# TRV_MRF49_U_V1_1_BF.net
KiCad netlist of a schematic drawn in EAGLE
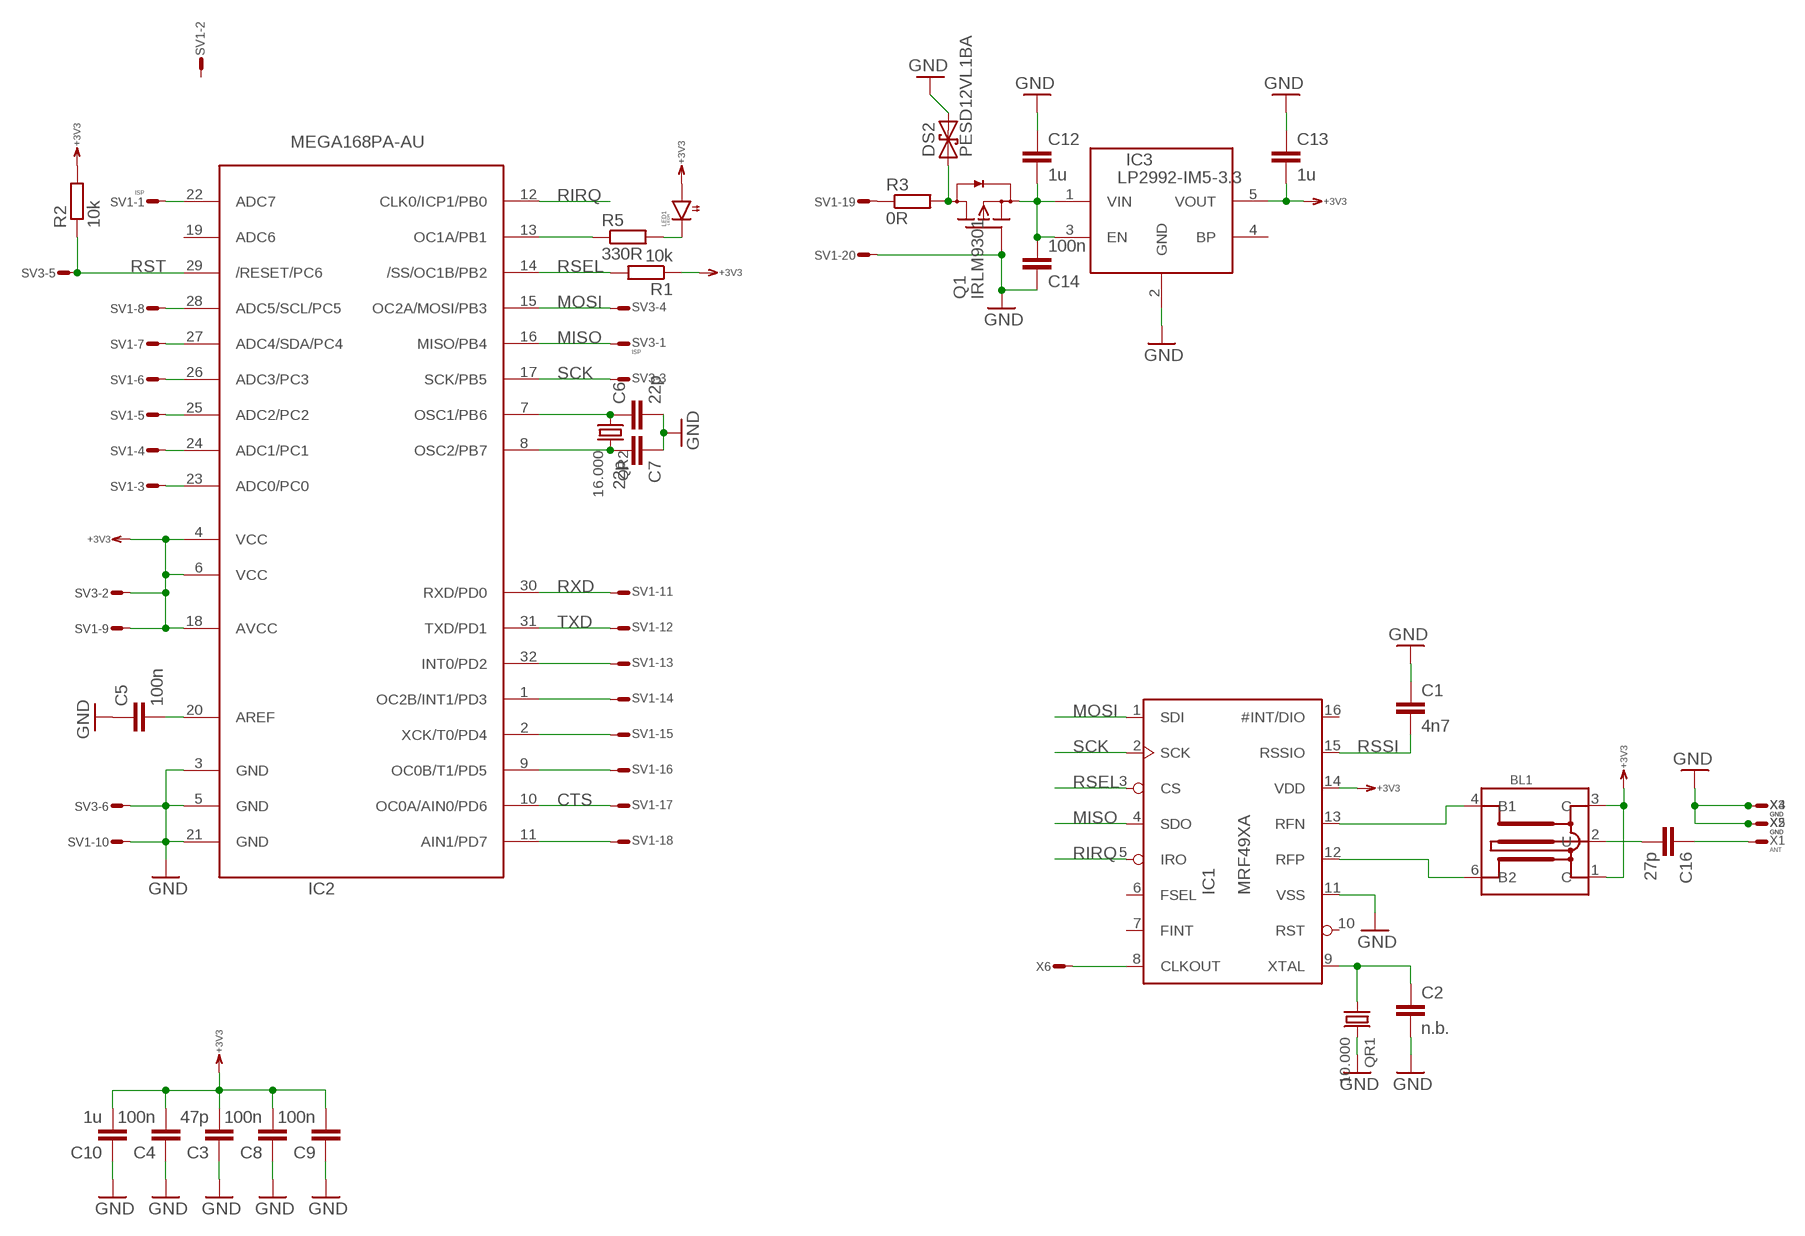
[diagram p0: schematic, sheet 1]

(export (version "E")
  (design (tool "Eeschema 10.0.6"))
  (components
    (comp (ref "BL1")
      (value "BL1")
      (footprint "eagle-import:BL")
      (libsource (lib "eagle-import") (part "BL1"))
    )
    (comp (ref "C1")
      (value "4n7")
      (footprint "eagle-import:0603")
      (libsource (lib "eagle-import") (part "C0603"))
    )
    (comp (ref "C2")
      (value "n.b.")
      (footprint "eagle-import:0603")
      (libsource (lib "eagle-import") (part "C0603"))
    )
    (comp (ref "C3")
      (value "47p")
      (footprint "eagle-import:0603")
      (libsource (lib "eagle-import") (part "C0603"))
    )
    (comp (ref "C4")
      (value "100n")
      (footprint "eagle-import:0603")
      (libsource (lib "eagle-import") (part "C0603"))
    )
    (comp (ref "C5")
      (value "100n")
      (footprint "eagle-import:0603")
      (libsource (lib "eagle-import") (part "C0603"))
    )
    (comp (ref "C6")
      (value "22p")
      (footprint "eagle-import:0603")
      (libsource (lib "eagle-import") (part "C0603"))
    )
    (comp (ref "C7")
      (value "22p")
      (footprint "eagle-import:0603")
      (libsource (lib "eagle-import") (part "C0603"))
    )
    (comp (ref "C8")
      (value "100n")
      (footprint "eagle-import:0603")
      (libsource (lib "eagle-import") (part "C0603"))
    )
    (comp (ref "C9")
      (value "100n")
      (footprint "eagle-import:0603")
      (libsource (lib "eagle-import") (part "C0603"))
    )
    (comp (ref "C10")
      (value "1u")
      (footprint "eagle-import:0603")
      (libsource (lib "eagle-import") (part "C0603"))
    )
    (comp (ref "C12")
      (value "1u")
      (footprint "eagle-import:0603")
      (libsource (lib "eagle-import") (part "C0603"))
    )
    (comp (ref "C13")
      (value "1u")
      (footprint "eagle-import:0603")
      (libsource (lib "eagle-import") (part "C0603"))
    )
    (comp (ref "C14")
      (value "100n")
      (footprint "eagle-import:0603")
      (libsource (lib "eagle-import") (part "C0603"))
    )
    (comp (ref "C16")
      (value "27p")
      (footprint "eagle-import:0603")
      (libsource (lib "eagle-import") (part "C0603"))
    )
    (comp (ref "DS2")
      (value "PESD12VL1BA")
      (footprint "eagle-import:SOD323")
      (libsource (lib "eagle-import") (part "TVS-U323"))
    )
    (comp (ref "IC1")
      (value "MRF49XA")
      (footprint "eagle-import:TSSOP16")
      (libsource (lib "eagle-import") (part "MRF49XA"))
    )
    (comp (ref "IC2")
      (value "MEGA168PA-AU")
      (footprint "eagle-import:TQFP32-08")
      (libsource (lib "eagle-import") (part "MEGA168PA"))
    )
    (comp (ref "IC3")
      (value "LP2992-IM5-3.3")
      (footprint "eagle-import:SOT23-5")
      (libsource (lib "eagle-import") (part "LDO"))
    )
    (comp (ref "LED1")
      (value "LEDR")
      (footprint "eagle-import:0603")
      (libsource (lib "eagle-import") (part "LED0603"))
    )
    (comp (ref "Q1")
      (value "IRLM9301")
      (footprint "eagle-import:SOT23")
      (libsource (lib "eagle-import") (part "FET-PDSOT23"))
    )
    (comp (ref "QR1")
      (value "10.000")
      (footprint "eagle-import:HC49U-V")
      (libsource (lib "eagle-import") (part "Q49UV"))
    )
    (comp (ref "QR2")
      (value "16.000")
      (footprint "eagle-import:HC49U-V")
      (libsource (lib "eagle-import") (part "Q49UV"))
    )
    (comp (ref "R1")
      (value "10k")
      (footprint "eagle-import:0603")
      (libsource (lib "eagle-import") (part "R0603"))
    )
    (comp (ref "R2")
      (value "10k")
      (footprint "eagle-import:0603")
      (libsource (lib "eagle-import") (part "R0603"))
    )
    (comp (ref "R3")
      (value "0R")
      (footprint "eagle-import:0603")
      (libsource (lib "eagle-import") (part "R0603"))
    )
    (comp (ref "R5")
      (value "330R")
      (footprint "eagle-import:0603")
      (libsource (lib "eagle-import") (part "R0603"))
    )
    (comp (ref "SV1")
      (value "ISP")
      (footprint "eagle-import:ML20")
      (libsource (lib "eagle-import") (part "ML20?E"))
    )
    (comp (ref "SV3")
      (value "ISP")
      (footprint "eagle-import:ML6")
      (libsource (lib "eagle-import") (part "ML6E"))
    )
    (comp (ref "X1")
      (value "ANT")
      (footprint "eagle-import:S2.54_1.27")
      (libsource (lib "eagle-import") (part "WIREPADS2.54/1.27"))
    )
    (comp (ref "X2")
      (value "GND")
      (footprint "eagle-import:S2.54_1.27")
      (libsource (lib "eagle-import") (part "WIREPADS2.54/1.27"))
    )
    (comp (ref "X3")
      (value "GND")
      (footprint "eagle-import:S2.54_1.27")
      (libsource (lib "eagle-import") (part "WIREPADS2.54/1.27"))
    )
    (comp (ref "X4")
      (value "GND")
      (footprint "eagle-import:S2.54_1.27")
      (libsource (lib "eagle-import") (part "WIREPADS2.54/1.27"))
    )
    (comp (ref "X5")
      (value "GND")
      (footprint "eagle-import:S2.54_1.27")
      (libsource (lib "eagle-import") (part "WIREPADS2.54/1.27"))
    )
    (comp (ref "X6")
      (value "WIREPADR")
      (footprint "eagle-import:S1.27R")
      (libsource (lib "eagle-import") (part "WIREPADR"))
    )
  )
  (nets
    (net (code "1") (name "+3V3") (class "Default")
      (node (ref "BL1") (pin "1") (pinfunction "C_1") (pintype "bidirectional"))
      (node (ref "BL1") (pin "3") (pinfunction "C_3") (pintype "bidirectional"))
      (node (ref "C10") (pin "2") (pinfunction "2_2") (pintype "passive"))
      (node (ref "C13") (pin "2") (pinfunction "2_2") (pintype "passive"))
      (node (ref "C3") (pin "2") (pinfunction "2_2") (pintype "passive"))
      (node (ref "C4") (pin "2") (pinfunction "2_2") (pintype "passive"))
      (node (ref "C8") (pin "2") (pinfunction "2_2") (pintype "passive"))
      (node (ref "C9") (pin "2") (pinfunction "2_2") (pintype "passive"))
      (node (ref "IC1") (pin "14") (pinfunction "VDD_14") (pintype "input"))
      (node (ref "IC2") (pin "18") (pinfunction "AVCC_18") (pintype "bidirectional"))
      (node (ref "IC2") (pin "4") (pinfunction "VCC_4") (pintype "bidirectional"))
      (node (ref "IC2") (pin "6") (pinfunction "VCC_6") (pintype "bidirectional"))
      (node (ref "IC3") (pin "5") (pinfunction "VOUT_5") (pintype "bidirectional"))
      (node (ref "LED1") (pin "1") (pinfunction "A_1") (pintype "bidirectional"))
      (node (ref "R1") (pin "1") (pinfunction "1_1") (pintype "passive"))
      (node (ref "R2") (pin "2") (pinfunction "2_2") (pintype "passive"))
      (node (ref "SV1") (pin "9") (pinfunction "S_9") (pintype "passive"))
      (node (ref "SV3") (pin "2") (pinfunction "S_2") (pintype "passive"))
    )
    (net (code "2") (name "/CTS") (class "Default")
      (node (ref "IC2") (pin "10") (pinfunction "OC0A/AIN0/PD6_10") (pintype "bidirectional"))
      (node (ref "SV1") (pin "17") (pinfunction "S_17") (pintype "passive"))
    )
    (net (code "3") (name "/MISO") (class "Default")
      (node (ref "IC1") (pin "4") (pinfunction "SDO_4") (pintype "output"))
      (node (ref "IC2") (pin "16") (pinfunction "MISO/PB4_16") (pintype "bidirectional"))
      (node (ref "SV3") (pin "1") (pinfunction "S_1") (pintype "passive"))
    )
    (net (code "4") (name "/MOSI") (class "Default")
      (node (ref "IC1") (pin "1") (pinfunction "SDI_1") (pintype "input"))
      (node (ref "IC2") (pin "15") (pinfunction "OC2A/MOSI/PB3_15") (pintype "bidirectional"))
      (node (ref "SV3") (pin "4") (pinfunction "S_4") (pintype "passive"))
    )
    (net (code "5") (name "/RIRQ") (class "Default")
      (node (ref "IC1") (pin "5") (pinfunction "IRO_5") (pintype "output"))
      (node (ref "IC2") (pin "12") (pinfunction "CLK0/ICP1/PB0_12") (pintype "bidirectional"))
    )
    (net (code "6") (name "/RSEL") (class "Default")
      (node (ref "IC1") (pin "3") (pinfunction "CS_3") (pintype "input"))
      (node (ref "IC2") (pin "14") (pinfunction "/SS/OC1B/PB2_14") (pintype "bidirectional"))
      (node (ref "R1") (pin "2") (pinfunction "2_2") (pintype "passive"))
    )
    (net (code "7") (name "/RSSI") (class "Default")
      (node (ref "C1") (pin "2") (pinfunction "2_2") (pintype "passive"))
      (node (ref "IC1") (pin "15") (pinfunction "RSSIO_15") (pintype "bidirectional"))
    )
    (net (code "8") (name "/RST") (class "Default")
      (node (ref "IC2") (pin "29") (pinfunction "/RESET/PC6_29") (pintype "bidirectional"))
      (node (ref "R2") (pin "1") (pinfunction "1_1") (pintype "passive"))
      (node (ref "SV3") (pin "5") (pinfunction "S_5") (pintype "passive"))
    )
    (net (code "9") (name "/RXD") (class "Default")
      (node (ref "IC2") (pin "30") (pinfunction "RXD/PD0_30") (pintype "bidirectional"))
      (node (ref "SV1") (pin "11") (pinfunction "S_11") (pintype "passive"))
    )
    (net (code "10") (name "/SCK") (class "Default")
      (node (ref "IC1") (pin "2") (pinfunction "SCK_2") (pintype "input"))
      (node (ref "IC2") (pin "17") (pinfunction "SCK/PB5_17") (pintype "bidirectional"))
      (node (ref "SV3") (pin "3") (pinfunction "S_3") (pintype "passive"))
    )
    (net (code "11") (name "/TXD") (class "Default")
      (node (ref "IC2") (pin "31") (pinfunction "TXD/PD1_31") (pintype "bidirectional"))
      (node (ref "SV1") (pin "12") (pinfunction "S_12") (pintype "passive"))
    )
    (net (code "12") (name "GND") (class "Default")
      (node (ref "C1") (pin "1") (pinfunction "1_1") (pintype "passive"))
      (node (ref "C10") (pin "1") (pinfunction "1_1") (pintype "passive"))
      (node (ref "C12") (pin "1") (pinfunction "1_1") (pintype "passive"))
      (node (ref "C13") (pin "1") (pinfunction "1_1") (pintype "passive"))
      (node (ref "C14") (pin "1") (pinfunction "1_1") (pintype "passive"))
      (node (ref "C2") (pin "2") (pinfunction "2_2") (pintype "passive"))
      (node (ref "C3") (pin "1") (pinfunction "1_1") (pintype "passive"))
      (node (ref "C4") (pin "1") (pinfunction "1_1") (pintype "passive"))
      (node (ref "C5") (pin "1") (pinfunction "1_1") (pintype "passive"))
      (node (ref "C6") (pin "2") (pinfunction "2_2") (pintype "passive"))
      (node (ref "C7") (pin "1") (pinfunction "1_1") (pintype "passive"))
      (node (ref "C8") (pin "1") (pinfunction "1_1") (pintype "passive"))
      (node (ref "C9") (pin "1") (pinfunction "1_1") (pintype "passive"))
      (node (ref "DS2") (pin "C") (pinfunction "2_C") (pintype "passive"))
      (node (ref "IC1") (pin "11") (pinfunction "VSS_11") (pintype "input"))
      (node (ref "IC2") (pin "21") (pinfunction "GND_21") (pintype "bidirectional"))
      (node (ref "IC2") (pin "3") (pinfunction "GND_3") (pintype "bidirectional"))
      (node (ref "IC2") (pin "5") (pinfunction "GND_5") (pintype "bidirectional"))
      (node (ref "IC3") (pin "2") (pinfunction "GND_2") (pintype "bidirectional"))
      (node (ref "Q1") (pin "1") (pinfunction "G_1") (pintype "passive"))
      (node (ref "QR1") (pin "2") (pinfunction "2_2") (pintype "passive"))
      (node (ref "SV1") (pin "10") (pinfunction "S_10") (pintype "passive"))
      (node (ref "SV1") (pin "20") (pinfunction "S_20") (pintype "passive"))
      (node (ref "SV3") (pin "6") (pinfunction "S_6") (pintype "passive"))
      (node (ref "X2") (pin "1") (pinfunction "S_1") (pintype "passive"))
      (node (ref "X3") (pin "1") (pinfunction "S_1") (pintype "passive"))
      (node (ref "X4") (pin "1") (pinfunction "S_1") (pintype "passive"))
      (node (ref "X5") (pin "1") (pinfunction "S_1") (pintype "passive"))
    )
    (net (code "13") (name "Net-(BL1-B1)") (class "Default")
      (node (ref "BL1") (pin "4") (pinfunction "B1_4") (pintype "bidirectional"))
      (node (ref "IC1") (pin "13") (pinfunction "RFN_13") (pintype "bidirectional"))
    )
    (net (code "14") (name "Net-(BL1-B2)") (class "Default")
      (node (ref "BL1") (pin "6") (pinfunction "B2_6") (pintype "bidirectional"))
      (node (ref "IC1") (pin "12") (pinfunction "RFP_12") (pintype "bidirectional"))
    )
    (net (code "15") (name "Net-(BL1-U)") (class "Default")
      (node (ref "BL1") (pin "2") (pinfunction "U_2") (pintype "bidirectional"))
      (node (ref "C16") (pin "2") (pinfunction "2_2") (pintype "passive"))
    )
    (net (code "16") (name "Net-(DS2-1)") (class "Default")
      (node (ref "DS2") (pin "A") (pinfunction "1_A") (pintype "passive"))
      (node (ref "Q1") (pin "3") (pinfunction "D_3") (pintype "passive"))
      (node (ref "R3") (pin "2") (pinfunction "2_2") (pintype "passive"))
    )
    (net (code "17") (name "Net-(IC1-CLKOUT)") (class "Default")
      (node (ref "IC1") (pin "8") (pinfunction "CLKOUT_8") (pintype "output"))
      (node (ref "X6") (pin "1") (pinfunction "S_1") (pintype "passive"))
    )
    (net (code "18") (name "Net-(IC1-XTAL)") (class "Default")
      (node (ref "C2") (pin "1") (pinfunction "1_1") (pintype "passive"))
      (node (ref "IC1") (pin "9") (pinfunction "XTAL_9") (pintype "input"))
      (node (ref "QR1") (pin "1") (pinfunction "1_1") (pintype "passive"))
    )
    (net (code "19") (name "Net-(IC2-ADC0{slash}PC0)") (class "Default")
      (node (ref "IC2") (pin "23") (pinfunction "ADC0/PC0_23") (pintype "bidirectional"))
      (node (ref "SV1") (pin "3") (pinfunction "S_3") (pintype "passive"))
    )
    (net (code "20") (name "Net-(IC2-ADC1{slash}PC1)") (class "Default")
      (node (ref "IC2") (pin "24") (pinfunction "ADC1/PC1_24") (pintype "bidirectional"))
      (node (ref "SV1") (pin "4") (pinfunction "S_4") (pintype "passive"))
    )
    (net (code "21") (name "Net-(IC2-ADC2{slash}PC2)") (class "Default")
      (node (ref "IC2") (pin "25") (pinfunction "ADC2/PC2_25") (pintype "bidirectional"))
      (node (ref "SV1") (pin "5") (pinfunction "S_5") (pintype "passive"))
    )
    (net (code "22") (name "Net-(IC2-ADC3{slash}PC3)") (class "Default")
      (node (ref "IC2") (pin "26") (pinfunction "ADC3/PC3_26") (pintype "bidirectional"))
      (node (ref "SV1") (pin "6") (pinfunction "S_6") (pintype "passive"))
    )
    (net (code "23") (name "Net-(IC2-ADC4{slash}SDA{slash}PC4)") (class "Default")
      (node (ref "IC2") (pin "27") (pinfunction "ADC4/SDA/PC4_27") (pintype "bidirectional"))
      (node (ref "SV1") (pin "7") (pinfunction "S_7") (pintype "passive"))
    )
    (net (code "24") (name "Net-(IC2-ADC5{slash}SCL{slash}PC5)") (class "Default")
      (node (ref "IC2") (pin "28") (pinfunction "ADC5/SCL/PC5_28") (pintype "bidirectional"))
      (node (ref "SV1") (pin "8") (pinfunction "S_8") (pintype "passive"))
    )
    (net (code "25") (name "Net-(IC2-ADC7)") (class "Default")
      (node (ref "IC2") (pin "22") (pinfunction "ADC7_22") (pintype "bidirectional"))
      (node (ref "SV1") (pin "1") (pinfunction "S_1") (pintype "passive"))
    )
    (net (code "26") (name "Net-(IC2-AIN1{slash}PD7)") (class "Default")
      (node (ref "IC2") (pin "11") (pinfunction "AIN1/PD7_11") (pintype "bidirectional"))
      (node (ref "SV1") (pin "18") (pinfunction "S_18") (pintype "passive"))
    )
    (net (code "27") (name "Net-(IC2-AREF)") (class "Default")
      (node (ref "C5") (pin "2") (pinfunction "2_2") (pintype "passive"))
      (node (ref "IC2") (pin "20") (pinfunction "AREF_20") (pintype "bidirectional"))
    )
    (net (code "28") (name "Net-(IC2-INT0{slash}PD2)") (class "Default")
      (node (ref "IC2") (pin "32") (pinfunction "INT0/PD2_32") (pintype "bidirectional"))
      (node (ref "SV1") (pin "13") (pinfunction "S_13") (pintype "passive"))
    )
    (net (code "29") (name "Net-(IC2-OC0B{slash}T1{slash}PD5)") (class "Default")
      (node (ref "IC2") (pin "9") (pinfunction "OC0B/T1/PD5_9") (pintype "bidirectional"))
      (node (ref "SV1") (pin "16") (pinfunction "S_16") (pintype "passive"))
    )
    (net (code "30") (name "Net-(IC2-OC1A{slash}PB1)") (class "Default")
      (node (ref "IC2") (pin "13") (pinfunction "OC1A/PB1_13") (pintype "bidirectional"))
      (node (ref "R5") (pin "1") (pinfunction "1_1") (pintype "passive"))
    )
    (net (code "31") (name "Net-(IC2-OC2B{slash}INT1{slash}PD3)") (class "Default")
      (node (ref "IC2") (pin "1") (pinfunction "OC2B/INT1/PD3_1") (pintype "bidirectional"))
      (node (ref "SV1") (pin "14") (pinfunction "S_14") (pintype "passive"))
    )
    (net (code "32") (name "Net-(IC2-OSC1{slash}PB6)") (class "Default")
      (node (ref "C6") (pin "1") (pinfunction "1_1") (pintype "passive"))
      (node (ref "IC2") (pin "7") (pinfunction "OSC1/PB6_7") (pintype "bidirectional"))
      (node (ref "QR2") (pin "1") (pinfunction "1_1") (pintype "passive"))
    )
    (net (code "33") (name "Net-(IC2-OSC2{slash}PB7)") (class "Default")
      (node (ref "C7") (pin "2") (pinfunction "2_2") (pintype "passive"))
      (node (ref "IC2") (pin "8") (pinfunction "OSC2/PB7_8") (pintype "bidirectional"))
      (node (ref "QR2") (pin "2") (pinfunction "2_2") (pintype "passive"))
    )
    (net (code "34") (name "Net-(IC2-XCK{slash}T0{slash}PD4)") (class "Default")
      (node (ref "IC2") (pin "2") (pinfunction "XCK/T0/PD4_2") (pintype "bidirectional"))
      (node (ref "SV1") (pin "15") (pinfunction "S_15") (pintype "passive"))
    )
    (net (code "35") (name "Net-(IC3-EN)") (class "Default")
      (node (ref "C12") (pin "2") (pinfunction "2_2") (pintype "passive"))
      (node (ref "C14") (pin "2") (pinfunction "2_2") (pintype "passive"))
      (node (ref "IC3") (pin "1") (pinfunction "VIN_1") (pintype "bidirectional"))
      (node (ref "IC3") (pin "3") (pinfunction "EN_3") (pintype "bidirectional"))
      (node (ref "Q1") (pin "2") (pinfunction "S_2") (pintype "passive"))
    )
    (net (code "36") (name "Net-(LED1-C)") (class "Default")
      (node (ref "LED1") (pin "2") (pinfunction "C_2") (pintype "bidirectional"))
      (node (ref "R5") (pin "2") (pinfunction "2_2") (pintype "passive"))
    )
    (net (code "37") (name "Net-(SV1K-S)") (class "Default")
      (node (ref "R3") (pin "1") (pinfunction "1_1") (pintype "passive"))
      (node (ref "SV1") (pin "19") (pinfunction "S_19") (pintype "passive"))
    )
    (net (code "38") (name "Net-(X1-S)") (class "Default")
      (node (ref "C16") (pin "1") (pinfunction "1_1") (pintype "passive"))
      (node (ref "X1") (pin "1") (pinfunction "S_1") (pintype "passive"))
    )
    (net (code "39") (name "unconnected-(IC1-#INT{slash}DIO-Pad16)") (class "Default")
      (node (ref "IC1") (pin "16") (pinfunction "#INT/DIO_16") (pintype "bidirectional"))
    )
    (net (code "40") (name "unconnected-(IC1-FINT-Pad7)") (class "Default")
      (node (ref "IC1") (pin "7") (pinfunction "FINT_7") (pintype "bidirectional"))
    )
    (net (code "41") (name "unconnected-(IC1-FSEL-Pad6)") (class "Default")
      (node (ref "IC1") (pin "6") (pinfunction "FSEL_6") (pintype "bidirectional"))
    )
    (net (code "42") (name "unconnected-(IC1-RST-Pad10)") (class "Default")
      (node (ref "IC1") (pin "10") (pinfunction "RST_10") (pintype "bidirectional"))
    )
    (net (code "43") (name "unconnected-(IC2-ADC6-Pad19)") (class "Default")
      (node (ref "IC2") (pin "19") (pinfunction "ADC6_19") (pintype "bidirectional"))
    )
    (net (code "44") (name "unconnected-(IC3-BP-Pad4)") (class "Default")
      (node (ref "IC3") (pin "4") (pinfunction "BP_4") (pintype "bidirectional"))
    )
    (net (code "45") (name "unconnected-(SV1L-S-Pad2)") (class "Default")
      (node (ref "SV1") (pin "2") (pinfunction "S_2") (pintype "passive"))
    )
  )
)
